# weichen-a-5.net
KiCad netlist of a schematic drawn in EAGLE
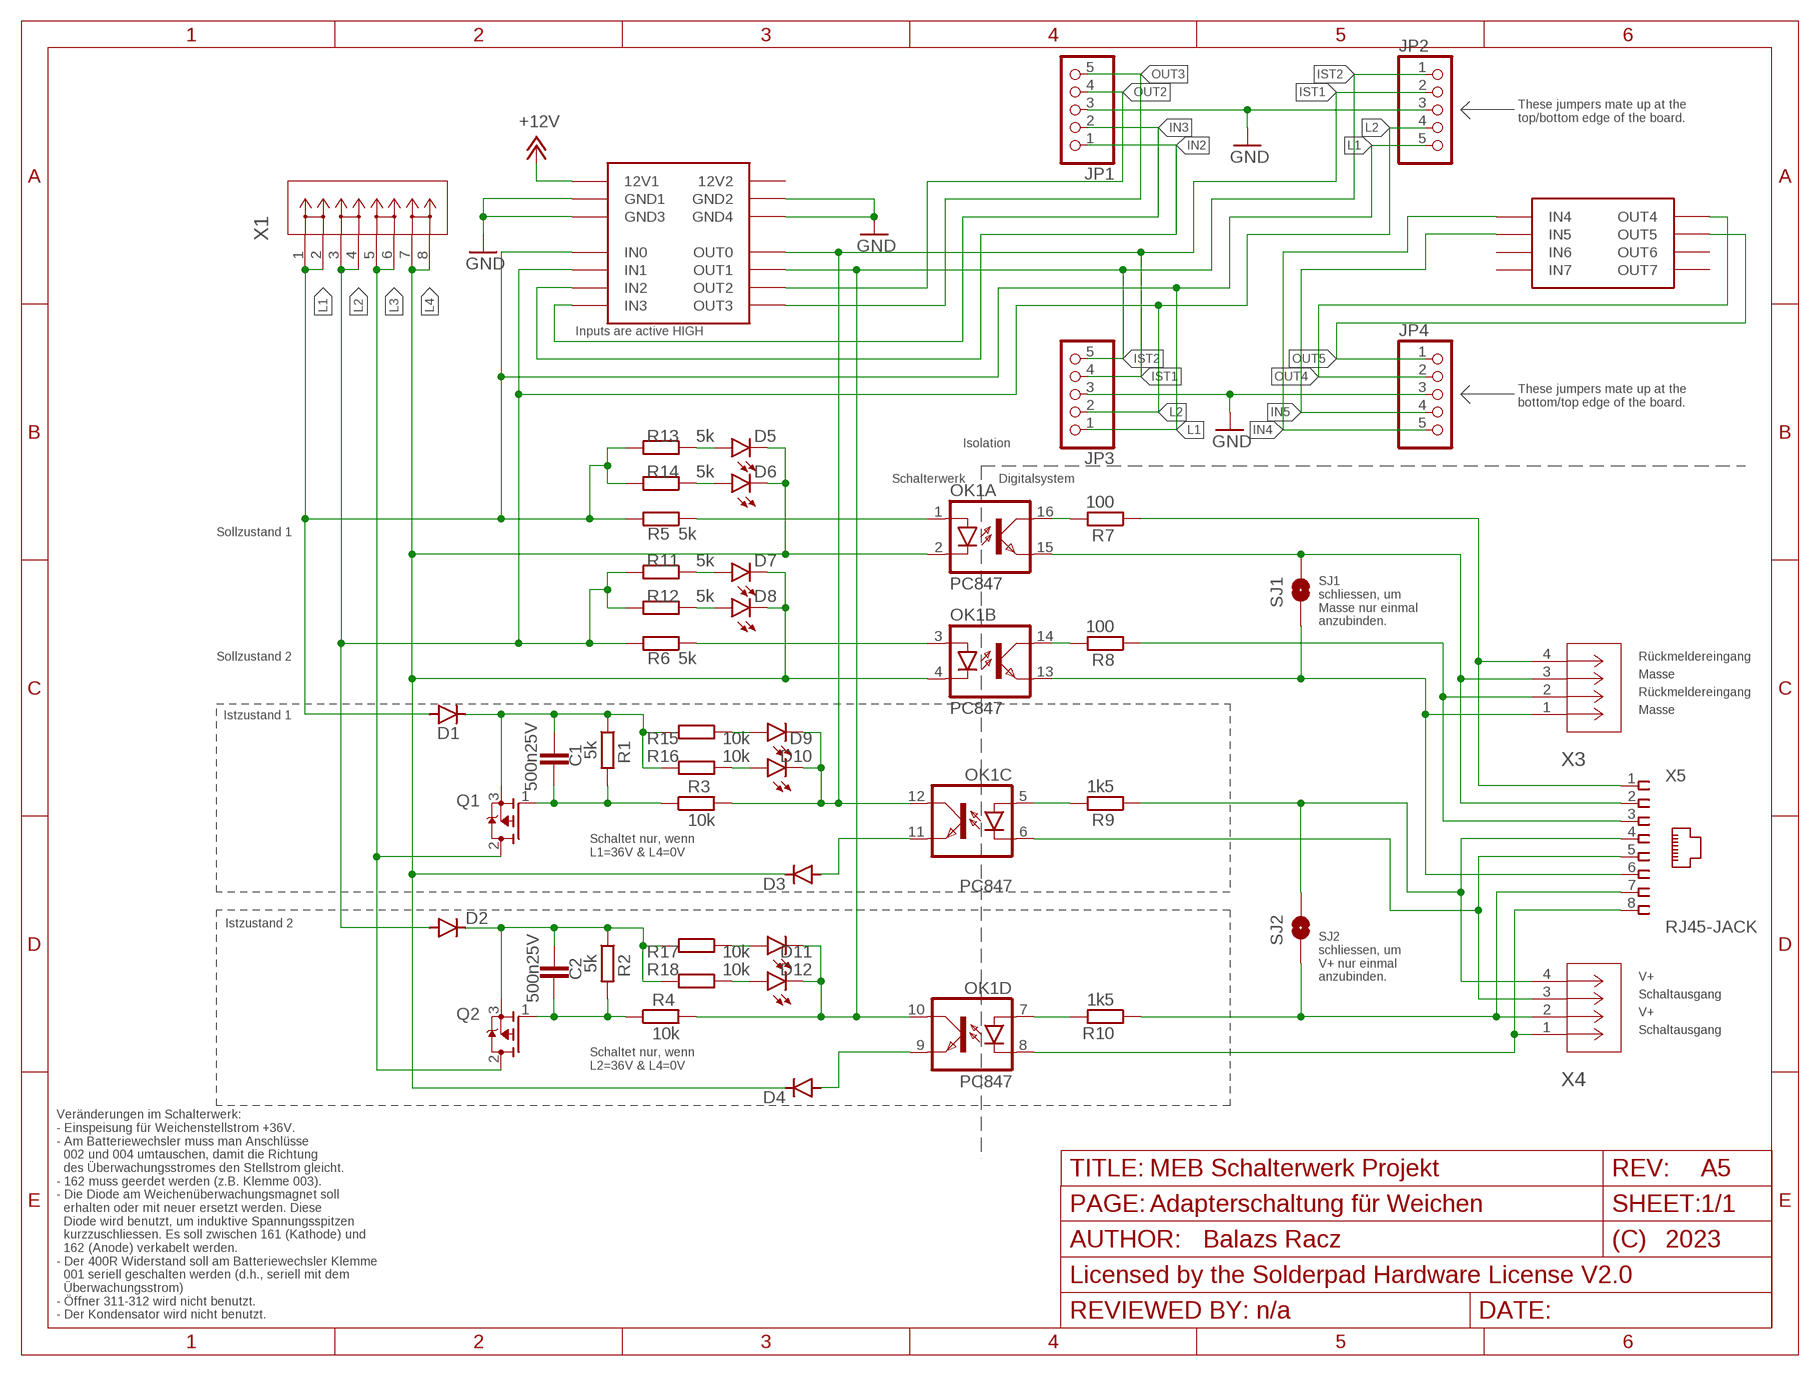
[diagram p0: schematic, sheet 1]

(export (version "E")
  (design (tool "Eeschema 10.0.6"))
  (components
    (comp (ref "C1")
      (value "500n25V")
      (footprint "eagle-import:C0805")
      (libsource (lib "eagle-import") (part "C-EUC0805"))
    )
    (comp (ref "C2")
      (value "500n25V")
      (footprint "eagle-import:C0805")
      (libsource (lib "eagle-import") (part "C-EUC0805"))
    )
    (comp (ref "D1")
      (value "DIODE-DO214AC")
      (footprint "eagle-import:DO214AC")
      (libsource (lib "eagle-import") (part "DIODE-DO214AC"))
    )
    (comp (ref "D2")
      (value "DIODE-DO214AC")
      (footprint "eagle-import:DO214AC")
      (libsource (lib "eagle-import") (part "DIODE-DO214AC"))
    )
    (comp (ref "D3")
      (value "DIODE-MINIMELF")
      (footprint "eagle-import:MINIMELF")
      (libsource (lib "eagle-import") (part "DIODE-MINIMELF"))
    )
    (comp (ref "D4")
      (value "DIODE-MINIMELF")
      (footprint "eagle-import:MINIMELF")
      (libsource (lib "eagle-import") (part "DIODE-MINIMELF"))
    )
    (comp (ref "D5")
      (value "LEDCHIPLED_0603")
      (footprint "eagle-import:CHIPLED_0603")
      (libsource (lib "eagle-import") (part "LEDCHIPLED_0603"))
    )
    (comp (ref "D6")
      (value "LEDHEADER")
      (footprint "eagle-import:LEDHEADER")
      (libsource (lib "eagle-import") (part "LEDHEADER"))
    )
    (comp (ref "D7")
      (value "LEDCHIPLED_0603")
      (footprint "eagle-import:CHIPLED_0603")
      (libsource (lib "eagle-import") (part "LEDCHIPLED_0603"))
    )
    (comp (ref "D8")
      (value "LEDHEADER")
      (footprint "eagle-import:LEDHEADER")
      (libsource (lib "eagle-import") (part "LEDHEADER"))
    )
    (comp (ref "D9")
      (value "LEDCHIPLED_0603")
      (footprint "eagle-import:CHIPLED_0603")
      (libsource (lib "eagle-import") (part "LEDCHIPLED_0603"))
    )
    (comp (ref "D10")
      (value "LEDHEADER")
      (footprint "eagle-import:LEDHEADER")
      (libsource (lib "eagle-import") (part "LEDHEADER"))
    )
    (comp (ref "D11")
      (value "LEDCHIPLED_0603")
      (footprint "eagle-import:CHIPLED_0603")
      (libsource (lib "eagle-import") (part "LEDCHIPLED_0603"))
    )
    (comp (ref "D12")
      (value "LEDHEADER")
      (footprint "eagle-import:LEDHEADER")
      (libsource (lib "eagle-import") (part "LEDHEADER"))
    )
    (comp (ref "JP1")
      (value "PINHD-1X5-EDGE")
      (footprint "eagle-import:1X05")
      (libsource (lib "eagle-import") (part "PINHD-1X5-EDGE"))
    )
    (comp (ref "JP2")
      (value "PINHD-1X5-EDGE")
      (footprint "eagle-import:1X05")
      (libsource (lib "eagle-import") (part "PINHD-1X5-EDGE"))
    )
    (comp (ref "JP3")
      (value "PINHD-1X5-EDGE")
      (footprint "eagle-import:1X05")
      (libsource (lib "eagle-import") (part "PINHD-1X5-EDGE"))
    )
    (comp (ref "JP4")
      (value "PINHD-1X5-EDGE")
      (footprint "eagle-import:1X05")
      (libsource (lib "eagle-import") (part "PINHD-1X5-EDGE"))
    )
    (comp (ref "OK1")
      (value "PC847")
      (footprint "eagle-import:DIL16")
      (libsource (lib "eagle-import") (part "PC847"))
    )
    (comp (ref "Q1")
      (value "P-MOSFET")
      (footprint "eagle-import:DPAK-2")
      (fields (field (name "MANUFACTURER") "Infineon"))
      (libsource (lib "eagle-import") (part "P-MOSFET"))
    )
    (comp (ref "Q2")
      (value "P-MOSFET")
      (footprint "eagle-import:DPAK-2")
      (fields (field (name "MANUFACTURER") "Infineon"))
      (libsource (lib "eagle-import") (part "P-MOSFET"))
    )
    (comp (ref "R1")
      (value "5k")
      (footprint "eagle-import:R0805")
      (libsource (lib "eagle-import") (part "R-EU_R0805"))
    )
    (comp (ref "R2")
      (value "5k")
      (footprint "eagle-import:R0805")
      (libsource (lib "eagle-import") (part "R-EU_R0805"))
    )
    (comp (ref "R3")
      (value "10k")
      (footprint "eagle-import:R0805")
      (libsource (lib "eagle-import") (part "R-EU_R0805"))
    )
    (comp (ref "R4")
      (value "10k")
      (footprint "eagle-import:R0805")
      (libsource (lib "eagle-import") (part "R-EU_R0805"))
    )
    (comp (ref "R5")
      (value "5k")
      (footprint "eagle-import:R0805")
      (libsource (lib "eagle-import") (part "R-EU_R0805"))
    )
    (comp (ref "R6")
      (value "5k")
      (footprint "eagle-import:R0805")
      (libsource (lib "eagle-import") (part "R-EU_R0805"))
    )
    (comp (ref "R7")
      (value "100")
      (footprint "eagle-import:R0805")
      (libsource (lib "eagle-import") (part "R-EU_R0805"))
    )
    (comp (ref "R8")
      (value "100")
      (footprint "eagle-import:R0805")
      (libsource (lib "eagle-import") (part "R-EU_R0805"))
    )
    (comp (ref "R9")
      (value "1k5")
      (footprint "eagle-import:R0805")
      (libsource (lib "eagle-import") (part "R-EU_R0805"))
    )
    (comp (ref "R10")
      (value "1k5")
      (footprint "eagle-import:R0805")
      (libsource (lib "eagle-import") (part "R-EU_R0805"))
    )
    (comp (ref "R11")
      (value "5k")
      (footprint "eagle-import:R0805")
      (libsource (lib "eagle-import") (part "R-EU_R0805"))
    )
    (comp (ref "R12")
      (value "5k")
      (footprint "eagle-import:R0805")
      (libsource (lib "eagle-import") (part "R-EU_R0805"))
    )
    (comp (ref "R13")
      (value "5k")
      (footprint "eagle-import:R0805")
      (libsource (lib "eagle-import") (part "R-EU_R0805"))
    )
    (comp (ref "R14")
      (value "5k")
      (footprint "eagle-import:R0805")
      (libsource (lib "eagle-import") (part "R-EU_R0805"))
    )
    (comp (ref "R15")
      (value "10k")
      (footprint "eagle-import:R0805")
      (libsource (lib "eagle-import") (part "R-EU_R0805"))
    )
    (comp (ref "R16")
      (value "10k")
      (footprint "eagle-import:R0805")
      (libsource (lib "eagle-import") (part "R-EU_R0805"))
    )
    (comp (ref "R17")
      (value "10k")
      (footprint "eagle-import:R0805")
      (libsource (lib "eagle-import") (part "R-EU_R0805"))
    )
    (comp (ref "R18")
      (value "10k")
      (footprint "eagle-import:R0805")
      (libsource (lib "eagle-import") (part "R-EU_R0805"))
    )
    (comp (ref "SJ1")
      (value "SJRND2")
      (footprint "eagle-import:SJ_RND2")
      (libsource (lib "eagle-import") (part "SJRND2"))
    )
    (comp (ref "SJ2")
      (value "SJRND2")
      (footprint "eagle-import:SJ_RND2")
      (libsource (lib "eagle-import") (part "SJRND2"))
    )
    (comp (ref "X1")
      (value "PHNX_4P_508CONN_1017493")
      (footprint "eagle-import:PHNX_4P_508")
      (fields
        (field (name "MANUFACTURER_PART_NUMBER") "1017505")
        (field (name "COPYRIGHT") "Copyright (C) 2023 Ultra Librarian. All rights reserved.")
      )
      (libsource (lib "eagle-import") (part "PHNX_4P_508CONN_1017493"))
    )
    (comp (ref "X2")
      (value "IO-HAT")
      (footprint "eagle-import:IOBOARD")
      (libsource (lib "eagle-import") (part "IO-HAT"))
    )
    (comp (ref "X3")
      (value "PHNX_4P_350CONN_1984989_PXC")
      (footprint "eagle-import:PHNX_4P_350")
      (fields
        (field (name "MANUFACTURER_PART_NUMBER") "1984989")
        (field (name "COPYRIGHT") "Copyright (C) 2023 Ultra Librarian. All rights reserved.")
      )
      (libsource (lib "eagle-import") (part "PHNX_4P_350CONN_1984989_PXC"))
    )
    (comp (ref "X4")
      (value "PHNX_4P_350CONN_1984989_PXC")
      (footprint "eagle-import:PHNX_4P_350")
      (fields
        (field (name "MANUFACTURER_PART_NUMBER") "1984989")
        (field (name "COPYRIGHT") "Copyright (C) 2023 Ultra Librarian. All rights reserved.")
      )
      (libsource (lib "eagle-import") (part "PHNX_4P_350CONN_1984989_PXC"))
    )
    (comp (ref "X5")
      (value "RJ45-JACK")
      (footprint "eagle-import:RJ45-PULSE-E5J88")
      (libsource (lib "eagle-import") (part "RJ45-JACKRJ45-PULSE-E5J00"))
    )
  )
  (nets
    (net (code "1") (name "+12V") (class "Default")
      (node (ref "X2") (pin "P$1") (pinfunction "12V1_P$1") (pintype "power_in"))
    )
    (net (code "2") (name "/12V2") (class "Default")
      (node (ref "X2") (pin "P$22") (pinfunction "12V2_P$22") (pintype "power_in"))
    )
    (net (code "3") (name "GND") (class "Default")
      (node (ref "JP1") (pin "3") (pinfunction "3_3") (pintype "passive"))
      (node (ref "JP2") (pin "3") (pinfunction "3_3") (pintype "passive"))
      (node (ref "JP3") (pin "3") (pinfunction "3_3") (pintype "passive"))
      (node (ref "JP4") (pin "3") (pinfunction "3_3") (pintype "passive"))
      (node (ref "X2") (pin "P$11") (pinfunction "GND3_P$11") (pintype "power_in"))
      (node (ref "X2") (pin "P$12") (pinfunction "GND4_P$12") (pintype "power_in"))
      (node (ref "X2") (pin "P$2") (pinfunction "GND1_P$2") (pintype "power_in"))
      (node (ref "X2") (pin "P$21") (pinfunction "GND2_P$21") (pintype "power_in"))
    )
    (net (code "4") (name "IN2") (class "Default")
      (node (ref "JP1") (pin "1") (pinfunction "1_1") (pintype "passive"))
      (node (ref "X2") (pin "P$5") (pinfunction "IN2_P$5") (pintype "input"))
    )
    (net (code "5") (name "IN3") (class "Default")
      (node (ref "JP1") (pin "2") (pinfunction "2_2") (pintype "passive"))
      (node (ref "X2") (pin "P$6") (pinfunction "IN3_P$6") (pintype "input"))
    )
    (net (code "6") (name "IN4") (class "Default")
      (node (ref "JP4") (pin "5") (pinfunction "5_5") (pintype "passive"))
      (node (ref "X2") (pin "P$7") (pinfunction "IN4_P$7") (pintype "input"))
    )
    (net (code "7") (name "IN5") (class "Default")
      (node (ref "JP4") (pin "4") (pinfunction "4_4") (pintype "passive"))
      (node (ref "X2") (pin "P$8") (pinfunction "IN5_P$8") (pintype "input"))
    )
    (net (code "8") (name "IST1") (class "Default")
      (node (ref "D10") (pin "C") (pinfunction "C_C") (pintype "passive"))
      (node (ref "D9") (pin "C") (pinfunction "C_C") (pintype "passive"))
      (node (ref "JP2") (pin "2") (pinfunction "2_2") (pintype "passive"))
      (node (ref "JP3") (pin "4") (pinfunction "4_4") (pintype "passive"))
      (node (ref "OK1") (pin "12") (pinfunction "COL_12") (pintype "passive"))
      (node (ref "R3") (pin "2") (pinfunction "2_2") (pintype "passive"))
      (node (ref "X2") (pin "P$20") (pinfunction "OUT0_P$20") (pintype "open_collector"))
    )
    (net (code "9") (name "IST2") (class "Default")
      (node (ref "D11") (pin "C") (pinfunction "C_C") (pintype "passive"))
      (node (ref "D12") (pin "C") (pinfunction "C_C") (pintype "passive"))
      (node (ref "JP2") (pin "1") (pinfunction "1_1") (pintype "passive"))
      (node (ref "JP3") (pin "5") (pinfunction "5_5") (pintype "passive"))
      (node (ref "OK1") (pin "10") (pinfunction "COL_10") (pintype "passive"))
      (node (ref "R4") (pin "2") (pinfunction "2_2") (pintype "passive"))
      (node (ref "X2") (pin "P$19") (pinfunction "OUT1_P$19") (pintype "open_collector"))
    )
    (net (code "10") (name "L1") (class "Default")
      (node (ref "D1") (pin "A") (pinfunction "A_A") (pintype "passive"))
      (node (ref "JP2") (pin "5") (pinfunction "5_5") (pintype "passive"))
      (node (ref "JP3") (pin "1") (pinfunction "1_1") (pintype "passive"))
      (node (ref "R13") (pin "2") (pinfunction "2_2") (pintype "passive"))
      (node (ref "R14") (pin "2") (pinfunction "2_2") (pintype "passive"))
      (node (ref "R5") (pin "2") (pinfunction "2_2") (pintype "passive"))
      (node (ref "X1") (pin "1") (pinfunction "1_1") (pintype "passive"))
      (node (ref "X1") (pin "2") (pinfunction "2_2") (pintype "passive"))
      (node (ref "X2") (pin "P$3") (pinfunction "IN0_P$3") (pintype "input"))
    )
    (net (code "11") (name "L2") (class "Default")
      (node (ref "D2") (pin "A") (pinfunction "A_A") (pintype "passive"))
      (node (ref "JP2") (pin "4") (pinfunction "4_4") (pintype "passive"))
      (node (ref "JP3") (pin "2") (pinfunction "2_2") (pintype "passive"))
      (node (ref "R11") (pin "2") (pinfunction "2_2") (pintype "passive"))
      (node (ref "R12") (pin "2") (pinfunction "2_2") (pintype "passive"))
      (node (ref "R6") (pin "2") (pinfunction "2_2") (pintype "passive"))
      (node (ref "X1") (pin "3") (pinfunction "3_3") (pintype "passive"))
      (node (ref "X1") (pin "4") (pinfunction "4_4") (pintype "passive"))
      (node (ref "X2") (pin "P$4") (pinfunction "IN1_P$4") (pintype "input"))
    )
    (net (code "12") (name "L3") (class "Default")
      (node (ref "Q1") (pin "2") (pinfunction "D_2") (pintype "passive"))
      (node (ref "Q2") (pin "2") (pinfunction "D_2") (pintype "passive"))
      (node (ref "X1") (pin "5") (pinfunction "5_5") (pintype "passive"))
      (node (ref "X1") (pin "6") (pinfunction "6_6") (pintype "passive"))
    )
    (net (code "13") (name "L4") (class "Default")
      (node (ref "D3") (pin "C") (pinfunction "C_C") (pintype "passive"))
      (node (ref "D4") (pin "C") (pinfunction "C_C") (pintype "passive"))
      (node (ref "D5") (pin "C") (pinfunction "C_C") (pintype "passive"))
      (node (ref "D6") (pin "C") (pinfunction "C_C") (pintype "passive"))
      (node (ref "D7") (pin "C") (pinfunction "C_C") (pintype "passive"))
      (node (ref "D8") (pin "C") (pinfunction "C_C") (pintype "passive"))
      (node (ref "OK1") (pin "2") (pinfunction "C_2") (pintype "passive"))
      (node (ref "OK1") (pin "4") (pinfunction "C_4") (pintype "passive"))
      (node (ref "X1") (pin "7") (pinfunction "7_7") (pintype "passive"))
      (node (ref "X1") (pin "8") (pinfunction "8_8") (pintype "passive"))
    )
    (net (code "14") (name "Net-(D5-PadA)") (class "Default")
      (node (ref "D5") (pin "A") (pinfunction "A_A") (pintype "passive"))
      (node (ref "R13") (pin "1") (pinfunction "1_1") (pintype "passive"))
    )
    (net (code "15") (name "Net-(D6-PadA)") (class "Default")
      (node (ref "D6") (pin "A") (pinfunction "A_A") (pintype "passive"))
      (node (ref "R14") (pin "1") (pinfunction "1_1") (pintype "passive"))
    )
    (net (code "16") (name "Net-(D7-PadA)") (class "Default")
      (node (ref "D7") (pin "A") (pinfunction "A_A") (pintype "passive"))
      (node (ref "R11") (pin "1") (pinfunction "1_1") (pintype "passive"))
    )
    (net (code "17") (name "Net-(D8-PadA)") (class "Default")
      (node (ref "D8") (pin "A") (pinfunction "A_A") (pintype "passive"))
      (node (ref "R12") (pin "1") (pinfunction "1_1") (pintype "passive"))
    )
    (net (code "18") (name "Net-(D9-PadA)") (class "Default")
      (node (ref "D9") (pin "A") (pinfunction "A_A") (pintype "passive"))
      (node (ref "R15") (pin "1") (pinfunction "1_1") (pintype "passive"))
    )
    (net (code "19") (name "Net-(D10-PadA)") (class "Default")
      (node (ref "D10") (pin "A") (pinfunction "A_A") (pintype "passive"))
      (node (ref "R16") (pin "1") (pinfunction "1_1") (pintype "passive"))
    )
    (net (code "20") (name "Net-(D11-PadA)") (class "Default")
      (node (ref "D11") (pin "A") (pinfunction "A_A") (pintype "passive"))
      (node (ref "R17") (pin "1") (pinfunction "1_1") (pintype "passive"))
    )
    (net (code "21") (name "Net-(D12-PadA)") (class "Default")
      (node (ref "D12") (pin "A") (pinfunction "A_A") (pintype "passive"))
      (node (ref "R18") (pin "1") (pinfunction "1_1") (pintype "passive"))
    )
    (net (code "22") (name "Net-(OK1A-A)") (class "Default")
      (node (ref "OK1") (pin "1") (pinfunction "A_1") (pintype "passive"))
      (node (ref "R5") (pin "1") (pinfunction "1_1") (pintype "passive"))
    )
    (net (code "23") (name "Net-(OK1A-COL)") (class "Default")
      (node (ref "OK1") (pin "16") (pinfunction "COL_16") (pintype "passive"))
      (node (ref "R7") (pin "2") (pinfunction "2_2") (pintype "passive"))
    )
    (net (code "24") (name "Net-(OK1A-EMIT)") (class "Default")
      (node (ref "OK1") (pin "15") (pinfunction "EMIT_15") (pintype "passive"))
      (node (ref "SJ1") (pin "P$2") (pinfunction "2_P$2") (pintype "passive"))
      (node (ref "X3") (pin "3") (pinfunction "3_3") (pintype "passive"))
      (node (ref "X5") (pin "2") (pinfunction "2_2") (pintype "passive"))
    )
    (net (code "25") (name "Net-(OK1B-A)") (class "Default")
      (node (ref "OK1") (pin "3") (pinfunction "A_3") (pintype "passive"))
      (node (ref "R6") (pin "1") (pinfunction "1_1") (pintype "passive"))
    )
    (net (code "26") (name "Net-(OK1B-COL)") (class "Default")
      (node (ref "OK1") (pin "14") (pinfunction "COL_14") (pintype "passive"))
      (node (ref "R8") (pin "2") (pinfunction "2_2") (pintype "passive"))
    )
    (net (code "27") (name "Net-(OK1B-EMIT)") (class "Default")
      (node (ref "OK1") (pin "13") (pinfunction "EMIT_13") (pintype "passive"))
      (node (ref "SJ1") (pin "P$1") (pinfunction "1_P$1") (pintype "passive"))
      (node (ref "X3") (pin "1") (pinfunction "1_1") (pintype "passive"))
      (node (ref "X5") (pin "6") (pinfunction "6_6") (pintype "passive"))
    )
    (net (code "28") (name "Net-(OK1C-A)") (class "Default")
      (node (ref "OK1") (pin "5") (pinfunction "A_5") (pintype "passive"))
      (node (ref "R9") (pin "2") (pinfunction "2_2") (pintype "passive"))
    )
    (net (code "29") (name "Net-(OK1C-C)") (class "Default")
      (node (ref "OK1") (pin "6") (pinfunction "C_6") (pintype "passive"))
      (node (ref "X4") (pin "3") (pinfunction "3_3") (pintype "passive"))
      (node (ref "X5") (pin "5") (pinfunction "5_5") (pintype "passive"))
    )
    (net (code "30") (name "Net-(OK1C-EMIT)") (class "Default")
      (node (ref "D3") (pin "A") (pinfunction "A_A") (pintype "passive"))
      (node (ref "OK1") (pin "11") (pinfunction "EMIT_11") (pintype "passive"))
    )
    (net (code "31") (name "Net-(OK1D-A)") (class "Default")
      (node (ref "OK1") (pin "7") (pinfunction "A_7") (pintype "passive"))
      (node (ref "R10") (pin "2") (pinfunction "2_2") (pintype "passive"))
    )
    (net (code "32") (name "Net-(OK1D-C)") (class "Default")
      (node (ref "OK1") (pin "8") (pinfunction "C_8") (pintype "passive"))
      (node (ref "X4") (pin "1") (pinfunction "1_1") (pintype "passive"))
      (node (ref "X5") (pin "8") (pinfunction "8_8") (pintype "passive"))
    )
    (net (code "33") (name "Net-(OK1D-EMIT)") (class "Default")
      (node (ref "D4") (pin "A") (pinfunction "A_A") (pintype "passive"))
      (node (ref "OK1") (pin "9") (pinfunction "EMIT_9") (pintype "passive"))
    )
    (net (code "34") (name "Net-(Q1-G)") (class "Default")
      (node (ref "C1") (pin "2") (pinfunction "2_2") (pintype "passive"))
      (node (ref "Q1") (pin "1") (pinfunction "G_1") (pintype "passive"))
      (node (ref "R1") (pin "2") (pinfunction "2_2") (pintype "passive"))
      (node (ref "R3") (pin "1") (pinfunction "1_1") (pintype "passive"))
    )
    (net (code "35") (name "Net-(Q1-S)") (class "Default")
      (node (ref "C1") (pin "1") (pinfunction "1_1") (pintype "passive"))
      (node (ref "D1") (pin "C") (pinfunction "C_C") (pintype "passive"))
      (node (ref "Q1") (pin "3") (pinfunction "S_3") (pintype "passive"))
      (node (ref "R1") (pin "1") (pinfunction "1_1") (pintype "passive"))
      (node (ref "R15") (pin "2") (pinfunction "2_2") (pintype "passive"))
      (node (ref "R16") (pin "2") (pinfunction "2_2") (pintype "passive"))
    )
    (net (code "36") (name "Net-(Q2-G)") (class "Default")
      (node (ref "C2") (pin "2") (pinfunction "2_2") (pintype "passive"))
      (node (ref "Q2") (pin "1") (pinfunction "G_1") (pintype "passive"))
      (node (ref "R2") (pin "2") (pinfunction "2_2") (pintype "passive"))
      (node (ref "R4") (pin "1") (pinfunction "1_1") (pintype "passive"))
    )
    (net (code "37") (name "Net-(Q2-S)") (class "Default")
      (node (ref "C2") (pin "1") (pinfunction "1_1") (pintype "passive"))
      (node (ref "D2") (pin "C") (pinfunction "C_C") (pintype "passive"))
      (node (ref "Q2") (pin "3") (pinfunction "S_3") (pintype "passive"))
      (node (ref "R17") (pin "2") (pinfunction "2_2") (pintype "passive"))
      (node (ref "R18") (pin "2") (pinfunction "2_2") (pintype "passive"))
      (node (ref "R2") (pin "1") (pinfunction "1_1") (pintype "passive"))
    )
    (net (code "38") (name "Net-(R7-Pad1)") (class "Default")
      (node (ref "R7") (pin "1") (pinfunction "1_1") (pintype "passive"))
      (node (ref "X3") (pin "4") (pinfunction "4_4") (pintype "passive"))
      (node (ref "X5") (pin "1") (pinfunction "1_1") (pintype "passive"))
    )
    (net (code "39") (name "Net-(R8-Pad1)") (class "Default")
      (node (ref "R8") (pin "1") (pinfunction "1_1") (pintype "passive"))
      (node (ref "X3") (pin "2") (pinfunction "2_2") (pintype "passive"))
      (node (ref "X5") (pin "3") (pinfunction "3_3") (pintype "passive"))
    )
    (net (code "40") (name "Net-(SJ2-1)") (class "Default")
      (node (ref "R10") (pin "1") (pinfunction "1_1") (pintype "passive"))
      (node (ref "SJ2") (pin "P$1") (pinfunction "1_P$1") (pintype "passive"))
      (node (ref "X4") (pin "2") (pinfunction "2_2") (pintype "passive"))
      (node (ref "X5") (pin "7") (pinfunction "7_7") (pintype "passive"))
    )
    (net (code "41") (name "Net-(SJ2-2)") (class "Default")
      (node (ref "R9") (pin "1") (pinfunction "1_1") (pintype "passive"))
      (node (ref "SJ2") (pin "P$2") (pinfunction "2_P$2") (pintype "passive"))
      (node (ref "X4") (pin "4") (pinfunction "4_4") (pintype "passive"))
      (node (ref "X5") (pin "4") (pinfunction "4_4") (pintype "passive"))
    )
    (net (code "42") (name "OUT2") (class "Default")
      (node (ref "JP1") (pin "4") (pinfunction "4_4") (pintype "passive"))
      (node (ref "X2") (pin "P$18") (pinfunction "OUT2_P$18") (pintype "open_collector"))
    )
    (net (code "43") (name "OUT3") (class "Default")
      (node (ref "JP1") (pin "5") (pinfunction "5_5") (pintype "passive"))
      (node (ref "X2") (pin "P$17") (pinfunction "OUT3_P$17") (pintype "open_collector"))
    )
    (net (code "44") (name "OUT4") (class "Default")
      (node (ref "JP4") (pin "2") (pinfunction "2_2") (pintype "passive"))
      (node (ref "X2") (pin "P$16") (pinfunction "OUT4_P$16") (pintype "open_collector"))
    )
    (net (code "45") (name "OUT5") (class "Default")
      (node (ref "JP4") (pin "1") (pinfunction "1_1") (pintype "passive"))
      (node (ref "X2") (pin "P$15") (pinfunction "OUT5_P$15") (pintype "open_collector"))
    )
    (net (code "46") (name "unconnected-(X2B-IN6-PadP$9)") (class "Default")
      (node (ref "X2") (pin "P$9") (pinfunction "IN6_P$9") (pintype "input"))
    )
    (net (code "47") (name "unconnected-(X2B-IN7-PadP$10)") (class "Default")
      (node (ref "X2") (pin "P$10") (pinfunction "IN7_P$10") (pintype "input"))
    )
    (net (code "48") (name "unconnected-(X2B-OUT6-PadP$14)") (class "Default")
      (node (ref "X2") (pin "P$14") (pinfunction "OUT6_P$14") (pintype "open_collector"))
    )
    (net (code "49") (name "unconnected-(X2B-OUT7-PadP$13)") (class "Default")
      (node (ref "X2") (pin "P$13") (pinfunction "OUT7_P$13") (pintype "open_collector"))
    )
  )
)
